# 06_CAN_RS485.net
KiCad netlist of a schematic drawn in Altium Designer
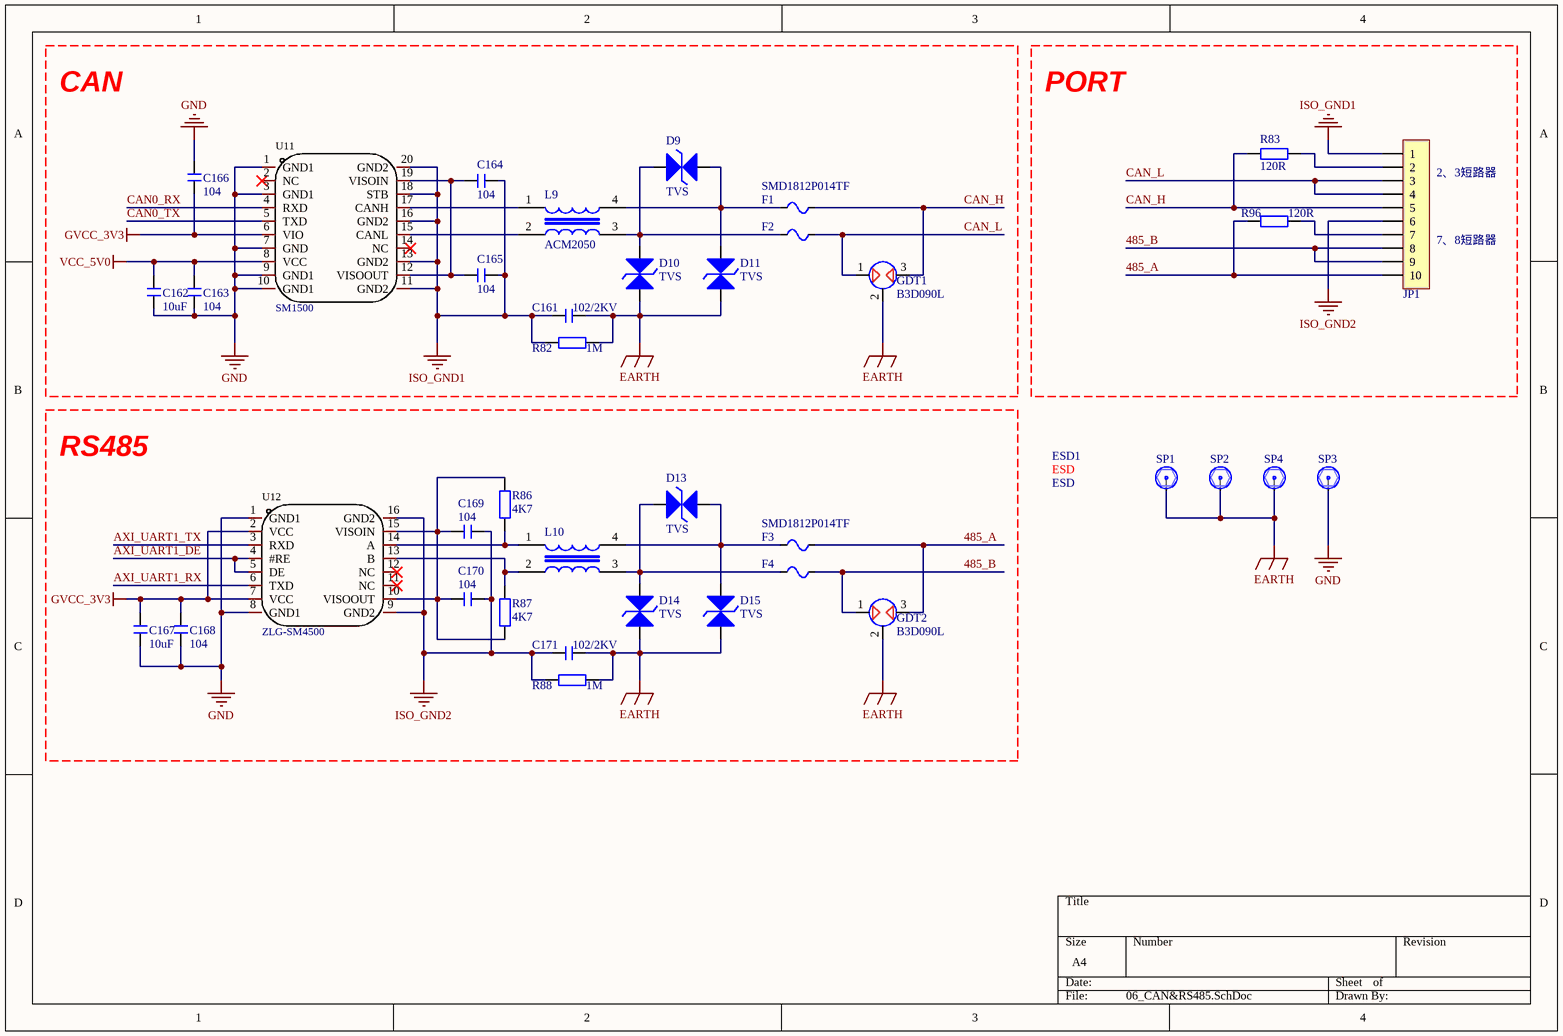
[diagram p0: 06_CAN&RS485.SchDoc]

(export (version "E")
  (design (tool "Eeschema 10.0.6"))
  (components
    (comp (ref "C161")
      (value "102/2KV")
      (footprint "C 1206")
      (description "无极性贴片电容")
      (fields (field (name "版权归属") "源创客"))
      (libsource (lib "STM32MP15x底板封装库V1.4") (part "C"))
    )
    (comp (ref "C162")
      (value "10uF")
      (footprint "C 0805")
      (description "无极性贴片电容")
      (fields (field (name "版权归属") "源创客"))
      (libsource (lib "STM32MP15x底板封装库V1.4") (part "C"))
    )
    (comp (ref "C163")
      (value "104")
      (footprint "C 0603")
      (description "无极性贴片电容")
      (fields (field (name "版权归属") "源创客"))
      (libsource (lib "STM32MP15x底板封装库V1.4") (part "C"))
    )
    (comp (ref "C164")
      (value "104")
      (footprint "C 0603")
      (description "无极性贴片电容")
      (fields (field (name "版权归属") "源创客"))
      (libsource (lib "STM32MP15x底板封装库V1.4") (part "C"))
    )
    (comp (ref "C165")
      (value "104")
      (footprint "C 0603")
      (description "无极性贴片电容")
      (fields (field (name "版权归属") "源创客"))
      (libsource (lib "STM32MP15x底板封装库V1.4") (part "C"))
    )
    (comp (ref "C166")
      (value "104")
      (footprint "C 0603")
      (description "无极性贴片电容")
      (fields (field (name "版权归属") "源创客"))
      (libsource (lib "STM32MP15x底板封装库V1.4") (part "C"))
    )
    (comp (ref "C167")
      (value "10uF")
      (footprint "C 0805")
      (description "无极性贴片电容")
      (fields (field (name "版权归属") "源创客"))
      (libsource (lib "STM32MP15x底板封装库V1.4") (part "C"))
    )
    (comp (ref "C168")
      (value "104")
      (footprint "C 0603")
      (description "无极性贴片电容")
      (fields (field (name "版权归属") "源创客"))
      (libsource (lib "STM32MP15x底板封装库V1.4") (part "C"))
    )
    (comp (ref "C169")
      (value "104")
      (footprint "C 0603")
      (description "无极性贴片电容")
      (fields (field (name "版权归属") "源创客"))
      (libsource (lib "STM32MP15x底板封装库V1.4") (part "C"))
    )
    (comp (ref "C170")
      (value "104")
      (footprint "C 0603")
      (description "无极性贴片电容")
      (fields (field (name "版权归属") "源创客"))
      (libsource (lib "STM32MP15x底板封装库V1.4") (part "C"))
    )
    (comp (ref "C171")
      (value "102/2KV")
      (footprint "C 1206")
      (description "无极性贴片电容")
      (fields (field (name "版权归属") "源创客"))
      (libsource (lib "STM32MP15x底板封装库V1.4") (part "C"))
    )
    (comp (ref "D9") (value "TVS") (footprint "SMA") (libsource (lib "TVS") (part "TVS")))
    (comp (ref "D10") (value "TVS") (footprint "SMA") (libsource (lib "TVS") (part "TVS")))
    (comp (ref "D11") (value "TVS") (footprint "SMA") (libsource (lib "TVS") (part "TVS")))
    (comp (ref "D13") (value "TVS") (footprint "SMA") (libsource (lib "TVS") (part "TVS")))
    (comp (ref "D14") (value "TVS") (footprint "SMA") (libsource (lib "TVS") (part "TVS")))
    (comp (ref "D15") (value "TVS") (footprint "SMA") (libsource (lib "TVS") (part "TVS")))
    (comp (ref "ESD1")
      (value "ESD")
      (footprint "ESD")
      (description "防静电")
      (fields (field (name "版权归属") "源创客"))
      (libsource (lib "STM32MP15x底板封装库V1.4") (part "ESD"))
    )
    (comp (ref "F1")
      (value "SMD1812P014TF")
      (footprint "PLCC-1812")
      (description "贴片保险丝")
      (fields (field (name "版权归属") "源创客"))
      (libsource (lib "STM32MP15x底板封装库V1.4") (part "FU"))
    )
    (comp (ref "F2")
      (value "SMD1812P014TF")
      (footprint "PLCC-1812")
      (description "贴片保险丝")
      (fields (field (name "版权归属") "源创客"))
      (libsource (lib "STM32MP15x底板封装库V1.4") (part "FU"))
    )
    (comp (ref "F3")
      (value "SMD1812P014TF")
      (footprint "PLCC-1812")
      (description "贴片保险丝")
      (fields (field (name "版权归属") "源创客"))
      (libsource (lib "STM32MP15x底板封装库V1.4") (part "FU"))
    )
    (comp (ref "F4")
      (value "SMD1812P014TF")
      (footprint "PLCC-1812")
      (description "贴片保险丝")
      (fields (field (name "版权归属") "源创客"))
      (libsource (lib "STM32MP15x底板封装库V1.4") (part "FU"))
    )
    (comp (ref "GDT1") (value "B3D090L") (footprint "B3D090L") (libsource (lib "B3D090L") (part "B3D090L")))
    (comp (ref "GDT2") (value "B3D090L") (footprint "B3D090L") (libsource (lib "B3D090L") (part "B3D090L")))
    (comp (ref "JP1")
      (value "HDR-1X10")
      (footprint "KF2EDGE_3.81_10P")
      (description "10P接插件")
      (fields (field (name "版权归属") "源创客"))
      (libsource (lib "4.5   - 接插件-脚距2.54") (part "Header 10"))
    )
    (comp (ref "L9") (value "ACM2050") (footprint "ACM2520") (libsource (lib "共模电感") (part "共模电感")))
    (comp (ref "L10") (value "共模电感") (footprint "ACM2520") (libsource (lib "共模电感") (part "共模电感")))
    (comp (ref "R82")
      (value "1M")
      (footprint "R 1206")
      (description "贴片电阻")
      (fields (field (name "版权归属") "源创客"))
      (libsource (lib "STM32MP15x底板封装库V1.4") (part "R"))
    )
    (comp (ref "R83")
      (value "120R")
      (footprint "R 1206")
      (description "贴片电阻")
      (fields (field (name "版权归属") "源创客"))
      (libsource (lib "STM32MP15x底板封装库V1.4") (part "R"))
    )
    (comp (ref "R86")
      (value "4K7")
      (footprint "R 0603")
      (description "贴片电阻")
      (fields (field (name "版权归属") "源创客"))
      (libsource (lib "STM32MP15x底板封装库V1.4") (part "R"))
    )
    (comp (ref "R87")
      (value "4K7")
      (footprint "R 0603")
      (description "贴片电阻")
      (fields (field (name "版权归属") "源创客"))
      (libsource (lib "STM32MP15x底板封装库V1.4") (part "R"))
    )
    (comp (ref "R88")
      (value "1M")
      (footprint "R 1206")
      (description "贴片电阻")
      (fields (field (name "版权归属") "源创客"))
      (libsource (lib "STM32MP15x底板封装库V1.4") (part "R"))
    )
    (comp (ref "R96")
      (value "120R")
      (footprint "R 1206")
      (description "贴片电阻")
      (fields (field (name "版权归属") "源创客"))
      (libsource (lib "STM32MP15x底板封装库V1.4") (part "R"))
    )
    (comp (ref "SP1")
      (value "M3铜柱")
      (footprint "M3-HOLE")
      (description "铜柱")
      (fields (field (name "版权归属") "源创客"))
      (libsource (lib "15.1 - 未分类器件") (part "铜柱大焊盘"))
    )
    (comp (ref "SP2")
      (value "M3铜柱")
      (footprint "M3-HOLE")
      (description "铜柱")
      (fields (field (name "版权归属") "源创客"))
      (libsource (lib "15.1 - 未分类器件") (part "铜柱大焊盘"))
    )
    (comp (ref "SP3")
      (value "M3铜柱")
      (footprint "M3-HOLE")
      (description "铜柱")
      (fields (field (name "版权归属") "源创客"))
      (libsource (lib "15.1 - 未分类器件") (part "铜柱大焊盘"))
    )
    (comp (ref "SP4")
      (value "M3铜柱")
      (footprint "M3-HOLE")
      (description "铜柱")
      (fields (field (name "版权归属") "源创客"))
      (libsource (lib "15.1 - 未分类器件") (part "铜柱大焊盘"))
    )
    (comp (ref "U11")
      (value "SM1500")
      (footprint "DFN-20_12,5x9.9")
      (fields (field (name "MANUFACTURER") "ZLG(致远电子)"))
      (libsource (lib "SM1500") (part "SM1500"))
    )
    (comp (ref "U12")
      (value "ZLG-SM4500")
      (footprint "DFN-16")
      (fields (field (name "MANUFACTURER") "MORNSUN(金升阳)") (field (name "MANUFACTURER PART") "TD541S485H"))
      (libsource (lib "ZLG-ZM4500") (part "ZLG-SM4500"))
    )
  )
  (nets
    (net (code "1") (name "/485_A") (class "Default")
      (node (ref "F3") (pin "2") (pinfunction "2_2") (pintype "passive"))
      (node (ref "GDT2") (pin "3") (pinfunction "3_3") (pintype "passive"))
      (node (ref "JP1") (pin "10") (pinfunction "10_10") (pintype "passive"))
      (node (ref "R96") (pin "2") (pinfunction "2_2") (pintype "passive"))
    )
    (net (code "2") (name "/485_B") (class "Default")
      (node (ref "F4") (pin "2") (pinfunction "2_2") (pintype "passive"))
      (node (ref "GDT2") (pin "1") (pinfunction "1_1") (pintype "passive"))
      (node (ref "JP1") (pin "8") (pinfunction "8_8") (pintype "passive"))
      (node (ref "JP1") (pin "9") (pinfunction "9_9") (pintype "passive"))
    )
    (net (code "3") (name "/AXI_UART1_DE") (class "Default")
      (node (ref "U12") (pin "4") (pinfunction "#RE_4") (pintype "passive"))
      (node (ref "U12") (pin "5") (pinfunction "DE_5") (pintype "passive"))
    )
    (net (code "4") (name "/AXI_UART1_RX") (class "Default")
      (node (ref "U12") (pin "6") (pinfunction "TXD_6") (pintype "passive"))
    )
    (net (code "5") (name "/AXI_UART1_TX") (class "Default")
      (node (ref "U12") (pin "3") (pinfunction "RXD_3") (pintype "passive"))
    )
    (net (code "6") (name "/CAN0_RX") (class "Default")
      (node (ref "U11") (pin "4") (pinfunction "RXD_4") (pintype "passive"))
    )
    (net (code "7") (name "/CAN0_TX") (class "Default")
      (node (ref "U11") (pin "5") (pinfunction "TXD_5") (pintype "passive"))
    )
    (net (code "8") (name "/CAN_H") (class "Default")
      (node (ref "F1") (pin "2") (pinfunction "2_2") (pintype "passive"))
      (node (ref "GDT1") (pin "3") (pinfunction "3_3") (pintype "passive"))
      (node (ref "JP1") (pin "5") (pinfunction "5_5") (pintype "passive"))
      (node (ref "R83") (pin "2") (pinfunction "2_2") (pintype "passive"))
    )
    (net (code "9") (name "/CAN_L") (class "Default")
      (node (ref "F2") (pin "2") (pinfunction "2_2") (pintype "passive"))
      (node (ref "GDT1") (pin "1") (pinfunction "1_1") (pintype "passive"))
      (node (ref "JP1") (pin "3") (pinfunction "3_3") (pintype "passive"))
      (node (ref "JP1") (pin "4") (pinfunction "4_4") (pintype "passive"))
    )
    (net (code "10") (name "EARTH") (class "Default")
      (node (ref "C161") (pin "2") (pinfunction "2_2") (pintype "passive"))
      (node (ref "C171") (pin "2") (pinfunction "2_2") (pintype "passive"))
      (node (ref "D10") (pin "1") (pinfunction "A_1") (pintype "passive"))
      (node (ref "D11") (pin "2") (pinfunction "K_2") (pintype "passive"))
      (node (ref "D14") (pin "1") (pinfunction "A_1") (pintype "passive"))
      (node (ref "D15") (pin "2") (pinfunction "K_2") (pintype "passive"))
      (node (ref "GDT1") (pin "2") (pinfunction "2_2") (pintype "passive"))
      (node (ref "GDT2") (pin "2") (pinfunction "2_2") (pintype "passive"))
      (node (ref "R82") (pin "2") (pinfunction "2_2") (pintype "passive"))
      (node (ref "R88") (pin "2") (pinfunction "2_2") (pintype "passive"))
      (node (ref "SP1") (pin "1") (pinfunction "1_1") (pintype "passive"))
      (node (ref "SP2") (pin "1") (pinfunction "1_1") (pintype "passive"))
      (node (ref "SP4") (pin "1") (pinfunction "1_1") (pintype "passive"))
    )
    (net (code "11") (name "GND") (class "Default")
      (node (ref "C162") (pin "1") (pinfunction "1_1") (pintype "passive"))
      (node (ref "C163") (pin "1") (pinfunction "1_1") (pintype "passive"))
      (node (ref "C166") (pin "2") (pinfunction "2_2") (pintype "passive"))
      (node (ref "C167") (pin "1") (pinfunction "1_1") (pintype "passive"))
      (node (ref "C168") (pin "1") (pinfunction "1_1") (pintype "passive"))
      (node (ref "SP3") (pin "1") (pinfunction "1_1") (pintype "passive"))
      (node (ref "U11") (pin "1") (pinfunction "GND1_1") (pintype "passive"))
      (node (ref "U11") (pin "10") (pinfunction "GND1_10") (pintype "passive"))
      (node (ref "U11") (pin "3") (pinfunction "GND1_3") (pintype "passive"))
      (node (ref "U11") (pin "7") (pinfunction "GND_7") (pintype "passive"))
      (node (ref "U11") (pin "9") (pinfunction "GND1_9") (pintype "passive"))
      (node (ref "U12") (pin "1") (pinfunction "GND1_1") (pintype "passive"))
      (node (ref "U12") (pin "8") (pinfunction "GND1_8") (pintype "passive"))
    )
    (net (code "12") (name "GVCC_3V3") (class "Default")
      (node (ref "C166") (pin "1") (pinfunction "1_1") (pintype "passive"))
      (node (ref "C167") (pin "2") (pinfunction "2_2") (pintype "passive"))
      (node (ref "C168") (pin "2") (pinfunction "2_2") (pintype "passive"))
      (node (ref "U11") (pin "6") (pinfunction "VIO_6") (pintype "passive"))
      (node (ref "U12") (pin "2") (pinfunction "VCC_2") (pintype "passive"))
      (node (ref "U12") (pin "7") (pinfunction "VCC_7") (pintype "passive"))
    )
    (net (code "13") (name "ISO_GND1") (class "Default")
      (node (ref "C161") (pin "1") (pinfunction "1_1") (pintype "passive"))
      (node (ref "C164") (pin "1") (pinfunction "1_1") (pintype "passive"))
      (node (ref "C165") (pin "2") (pinfunction "2_2") (pintype "passive"))
      (node (ref "JP1") (pin "1") (pinfunction "1_1") (pintype "passive"))
      (node (ref "R82") (pin "1") (pinfunction "1_1") (pintype "passive"))
      (node (ref "U11") (pin "11") (pinfunction "GND2_11") (pintype "passive"))
      (node (ref "U11") (pin "13") (pinfunction "GND2_13") (pintype "passive"))
      (node (ref "U11") (pin "16") (pinfunction "GND2_16") (pintype "passive"))
      (node (ref "U11") (pin "18") (pinfunction "STB_18") (pintype "passive"))
      (node (ref "U11") (pin "20") (pinfunction "GND2_20") (pintype "passive"))
    )
    (net (code "14") (name "ISO_GND2") (class "Default")
      (node (ref "C169") (pin "2") (pinfunction "2_2") (pintype "passive"))
      (node (ref "C170") (pin "2") (pinfunction "2_2") (pintype "passive"))
      (node (ref "C171") (pin "1") (pinfunction "1_1") (pintype "passive"))
      (node (ref "JP1") (pin "6") (pinfunction "6_6") (pintype "passive"))
      (node (ref "R88") (pin "1") (pinfunction "1_1") (pintype "passive"))
      (node (ref "U12") (pin "16") (pinfunction "GND2_16") (pintype "passive"))
      (node (ref "U12") (pin "9") (pinfunction "GND2_9") (pintype "passive"))
    )
    (net (code "15") (name "Net-(D10-K)") (class "Default")
      (node (ref "D10") (pin "2") (pinfunction "K_2") (pintype "passive"))
      (node (ref "D9") (pin "2") (pinfunction "K_2") (pintype "passive"))
      (node (ref "F2") (pin "1") (pinfunction "1_1") (pintype "passive"))
      (node (ref "L9") (pin "3") (pinfunction "3_3") (pintype "passive"))
    )
    (net (code "16") (name "Net-(D11-A)") (class "Default")
      (node (ref "D11") (pin "1") (pinfunction "A_1") (pintype "passive"))
      (node (ref "D9") (pin "1") (pinfunction "A_1") (pintype "passive"))
      (node (ref "F1") (pin "1") (pinfunction "1_1") (pintype "passive"))
      (node (ref "L9") (pin "4") (pinfunction "4_4") (pintype "passive"))
    )
    (net (code "17") (name "Net-(D13-A)") (class "Default")
      (node (ref "D13") (pin "1") (pinfunction "A_1") (pintype "passive"))
      (node (ref "D15") (pin "1") (pinfunction "A_1") (pintype "passive"))
      (node (ref "F3") (pin "1") (pinfunction "1_1") (pintype "passive"))
      (node (ref "L10") (pin "4") (pinfunction "4_4") (pintype "passive"))
    )
    (net (code "18") (name "Net-(D13-K)") (class "Default")
      (node (ref "D13") (pin "2") (pinfunction "K_2") (pintype "passive"))
      (node (ref "D14") (pin "2") (pinfunction "K_2") (pintype "passive"))
      (node (ref "F4") (pin "1") (pinfunction "1_1") (pintype "passive"))
      (node (ref "L10") (pin "3") (pinfunction "3_3") (pintype "passive"))
    )
    (net (code "19") (name "Net-(JP1-Pad2)") (class "Default")
      (node (ref "JP1") (pin "2") (pinfunction "2_2") (pintype "passive"))
      (node (ref "R83") (pin "1") (pinfunction "1_1") (pintype "passive"))
    )
    (net (code "20") (name "Net-(JP1-Pad7)") (class "Default")
      (node (ref "JP1") (pin "7") (pinfunction "7_7") (pintype "passive"))
      (node (ref "R96") (pin "1") (pinfunction "1_1") (pintype "passive"))
    )
    (net (code "21") (name "Net-(U11-CANH)") (class "Default")
      (node (ref "L9") (pin "1") (pinfunction "1_1") (pintype "passive"))
      (node (ref "U11") (pin "17") (pinfunction "CANH_17") (pintype "passive"))
    )
    (net (code "22") (name "Net-(U11-CANL)") (class "Default")
      (node (ref "L9") (pin "2") (pinfunction "2_2") (pintype "passive"))
      (node (ref "U11") (pin "15") (pinfunction "CANL_15") (pintype "passive"))
    )
    (net (code "23") (name "Net-(U11-VISOIN)") (class "Default")
      (node (ref "C164") (pin "2") (pinfunction "2_2") (pintype "passive"))
      (node (ref "C165") (pin "1") (pinfunction "1_1") (pintype "passive"))
      (node (ref "U11") (pin "12") (pinfunction "VISOOUT_12") (pintype "passive"))
      (node (ref "U11") (pin "19") (pinfunction "VISOIN_19") (pintype "passive"))
    )
    (net (code "24") (name "Net-(U12-A)") (class "Default")
      (node (ref "L10") (pin "1") (pinfunction "1_1") (pintype "passive"))
      (node (ref "R86") (pin "1") (pinfunction "1_1") (pintype "passive"))
      (node (ref "U12") (pin "14") (pinfunction "A_14") (pintype "passive"))
    )
    (net (code "25") (name "Net-(U12-B)") (class "Default")
      (node (ref "L10") (pin "2") (pinfunction "2_2") (pintype "passive"))
      (node (ref "R87") (pin "2") (pinfunction "2_2") (pintype "passive"))
      (node (ref "U12") (pin "13") (pinfunction "B_13") (pintype "passive"))
    )
    (net (code "26") (name "Net-(U12-VISOIN)") (class "Default")
      (node (ref "C169") (pin "1") (pinfunction "1_1") (pintype "passive"))
      (node (ref "C170") (pin "1") (pinfunction "1_1") (pintype "passive"))
      (node (ref "R86") (pin "2") (pinfunction "2_2") (pintype "passive"))
      (node (ref "R87") (pin "1") (pinfunction "1_1") (pintype "passive"))
      (node (ref "U12") (pin "10") (pinfunction "VISOOUT_10") (pintype "passive"))
      (node (ref "U12") (pin "15") (pinfunction "VISOIN_15") (pintype "passive"))
    )
    (net (code "27") (name "VCC_5V0") (class "Default")
      (node (ref "C162") (pin "2") (pinfunction "2_2") (pintype "passive"))
      (node (ref "C163") (pin "2") (pinfunction "2_2") (pintype "passive"))
      (node (ref "U11") (pin "8") (pinfunction "VCC_8") (pintype "passive"))
    )
    (net (code "28") (name "unconnected-(U11-NC-Pad2)") (class "Default")
      (node (ref "U11") (pin "2") (pinfunction "NC_2") (pintype "passive+no_connect"))
    )
    (net (code "29") (name "unconnected-(U11-NC-Pad14)") (class "Default")
      (node (ref "U11") (pin "14") (pinfunction "NC_14") (pintype "passive+no_connect"))
    )
    (net (code "30") (name "unconnected-(U12-NC-Pad11)") (class "Default")
      (node (ref "U12") (pin "11") (pinfunction "NC_11") (pintype "passive+no_connect"))
    )
    (net (code "31") (name "unconnected-(U12-NC-Pad12)") (class "Default")
      (node (ref "U12") (pin "12") (pinfunction "NC_12") (pintype "passive+no_connect"))
    )
  )
)
